# IndyShield.net
KiCad netlist of a schematic drawn in EAGLE
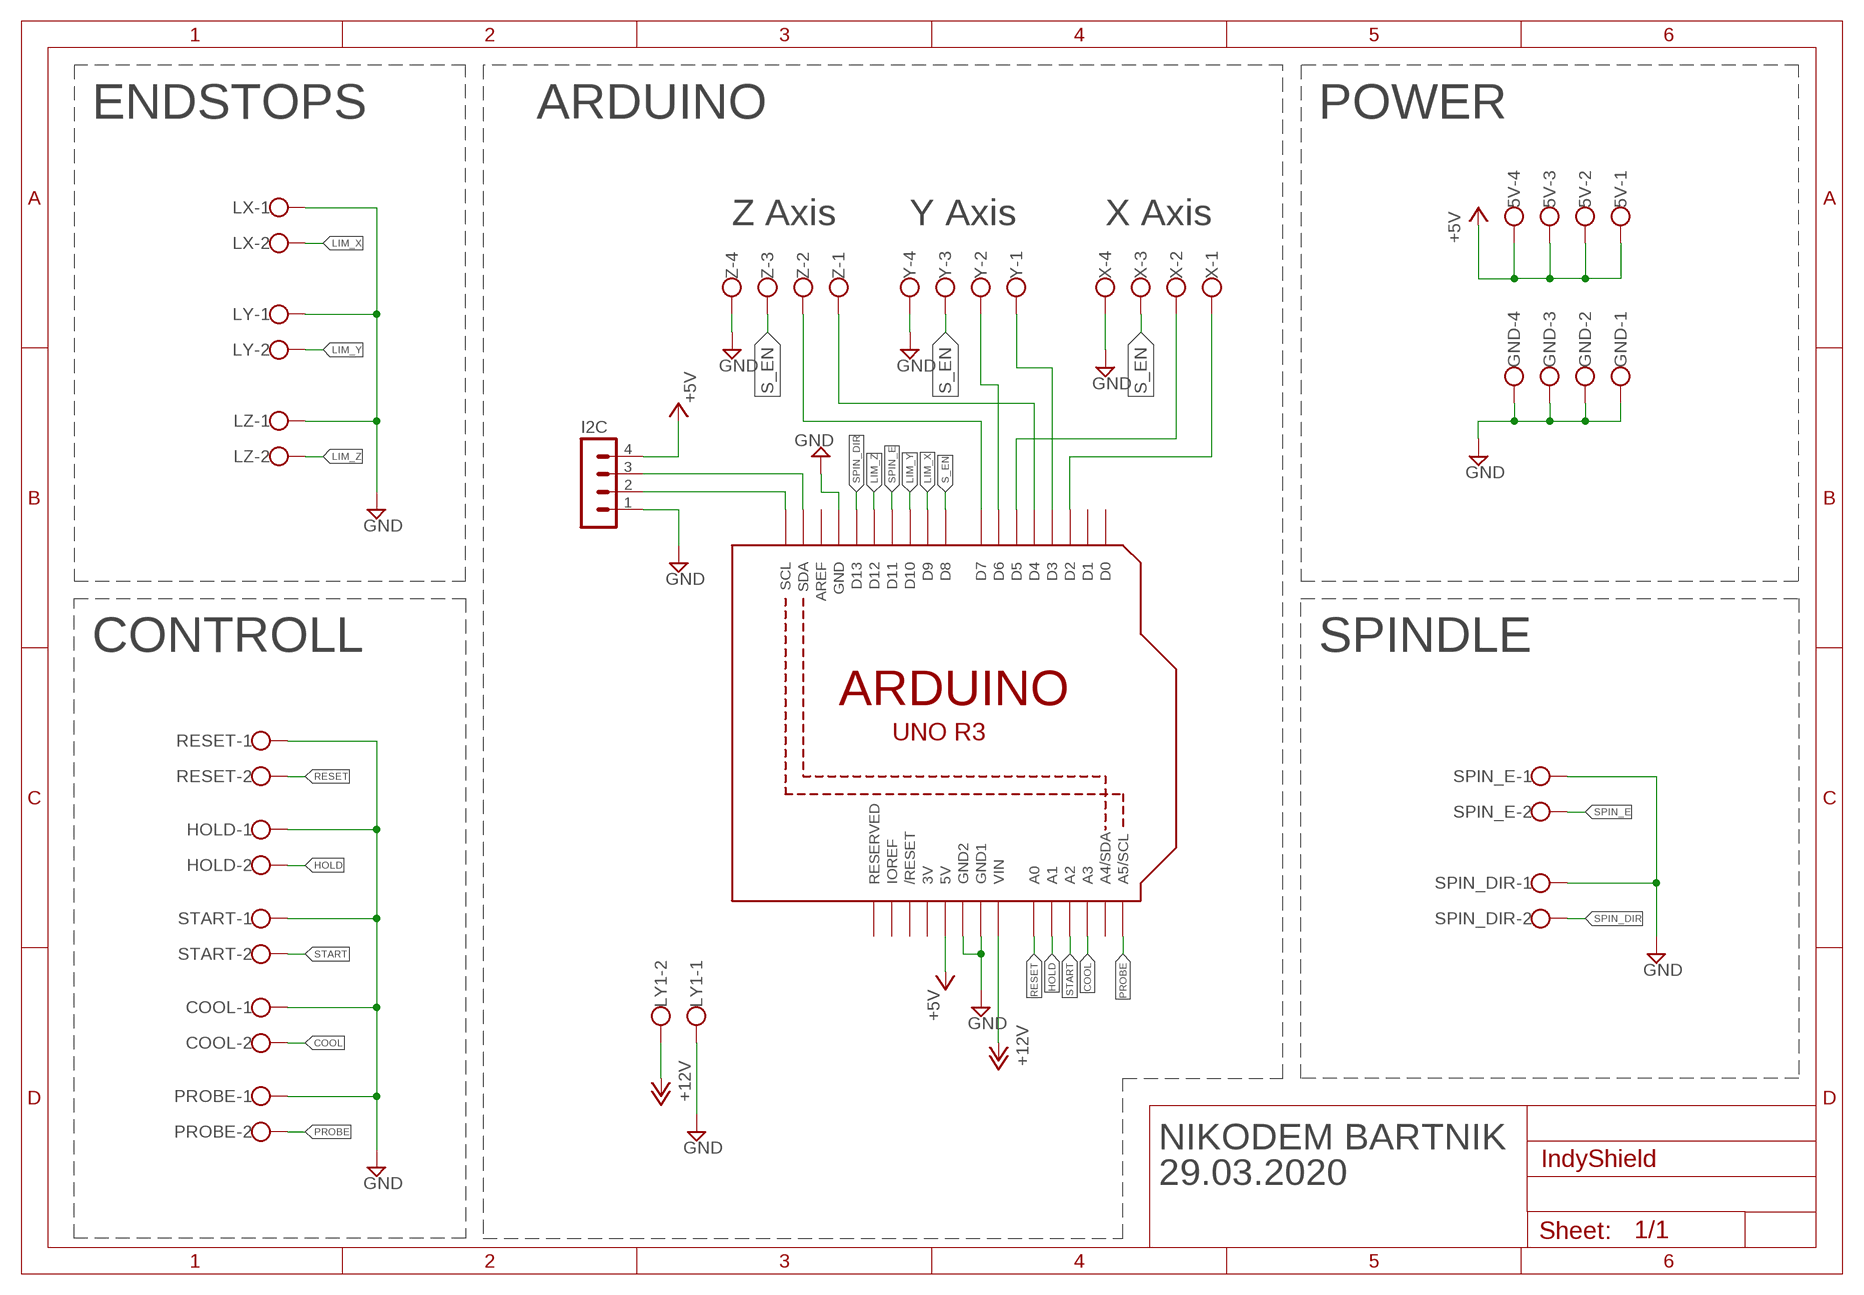
[diagram p0: schematic, sheet 1]

(export (version "E")
  (design (tool "Eeschema 10.0.6"))
  (components
    (comp (ref "5V")
      (value "W237-4")
      (footprint "eagle-import:W237-4")
      (libsource (lib "eagle-import") (part "W237-4"))
    )
    (comp (ref "COOL")
      (value "W237-102")
      (footprint "eagle-import:W237-102")
      (fields (field (name "MPN") "237-102"))
      (libsource (lib "eagle-import") (part "W237-102"))
    )
    (comp (ref "GND")
      (value "W237-4")
      (footprint "eagle-import:W237-4")
      (libsource (lib "eagle-import") (part "W237-4"))
    )
    (comp (ref "HOLD")
      (value "W237-102")
      (footprint "eagle-import:W237-102")
      (fields (field (name "MPN") "237-102"))
      (libsource (lib "eagle-import") (part "W237-102"))
    )
    (comp (ref "I2C")
      (value "MA04-1")
      (footprint "eagle-import:MA04-1")
      (libsource (lib "eagle-import") (part "MA04-1"))
    )
    (comp (ref "LX")
      (value "W237-102")
      (footprint "eagle-import:W237-102")
      (fields (field (name "MPN") "237-102"))
      (libsource (lib "eagle-import") (part "W237-102"))
    )
    (comp (ref "LY")
      (value "W237-102")
      (footprint "eagle-import:W237-102")
      (fields (field (name "MPN") "237-102"))
      (libsource (lib "eagle-import") (part "W237-102"))
    )
    (comp (ref "LY1")
      (value "W237-102")
      (footprint "eagle-import:W237-102")
      (fields (field (name "MPN") "237-102"))
      (libsource (lib "eagle-import") (part "W237-102"))
    )
    (comp (ref "LZ")
      (value "W237-102")
      (footprint "eagle-import:W237-102")
      (fields (field (name "MPN") "237-102"))
      (libsource (lib "eagle-import") (part "W237-102"))
    )
    (comp (ref "PROBE")
      (value "W237-102")
      (footprint "eagle-import:W237-102")
      (fields (field (name "MPN") "237-102"))
      (libsource (lib "eagle-import") (part "W237-102"))
    )
    (comp (ref "RESET")
      (value "W237-102")
      (footprint "eagle-import:W237-102")
      (fields (field (name "MPN") "237-102"))
      (libsource (lib "eagle-import") (part "W237-102"))
    )
    (comp (ref "SPIN_DIR")
      (value "W237-102")
      (footprint "eagle-import:W237-102")
      (fields (field (name "MPN") "237-102"))
      (libsource (lib "eagle-import") (part "W237-102"))
    )
    (comp (ref "SPIN_E")
      (value "W237-102")
      (footprint "eagle-import:W237-102")
      (fields (field (name "MPN") "237-102"))
      (libsource (lib "eagle-import") (part "W237-102"))
    )
    (comp (ref "START")
      (value "W237-102")
      (footprint "eagle-import:W237-102")
      (fields (field (name "MPN") "237-102"))
      (libsource (lib "eagle-import") (part "W237-102"))
    )
    (comp (ref "U1")
      (value "ARDUINOR3-BPLACE")
      (footprint "eagle-import:ARDUINOR3-BPLACE")
      (libsource (lib "eagle-import") (part "ARDUINOR3-BPLACE"))
    )
    (comp (ref "X")
      (value "W237-4")
      (footprint "eagle-import:W237-4")
      (libsource (lib "eagle-import") (part "W237-4"))
    )
    (comp (ref "Y")
      (value "W237-4")
      (footprint "eagle-import:W237-4")
      (libsource (lib "eagle-import") (part "W237-4"))
    )
    (comp (ref "Z")
      (value "W237-4")
      (footprint "eagle-import:W237-4")
      (libsource (lib "eagle-import") (part "W237-4"))
    )
  )
  (nets
    (net (code "1") (name "+5V") (class "Default")
      (node (ref "5V") (pin "1") (pinfunction "KL_1") (pintype "passive"))
      (node (ref "5V") (pin "2") (pinfunction "KL_2") (pintype "passive"))
      (node (ref "5V") (pin "3") (pinfunction "KL_3") (pintype "passive"))
      (node (ref "5V") (pin "4") (pinfunction "KL_4") (pintype "passive"))
      (node (ref "I2C") (pin "4") (pinfunction "4_4") (pintype "passive"))
      (node (ref "U1") (pin "5V") (pinfunction "5V_5V") (pintype "power_in"))
    )
    (net (code "2") (name "+12V") (class "Default")
      (node (ref "LY1") (pin "2") (pinfunction "KL_2") (pintype "passive"))
      (node (ref "U1") (pin "VIN") (pinfunction "VIN_VIN") (pintype "power_in"))
    )
    (net (code "3") (name "/3V") (class "Default")
      (node (ref "U1") (pin "3V") (pinfunction "3V_3V") (pintype "power_in"))
    )
    (net (code "4") (name "COOL") (class "Default")
      (node (ref "COOL") (pin "2") (pinfunction "KL_2") (pintype "passive"))
      (node (ref "U1") (pin "A3") (pinfunction "A3_A3") (pintype "bidirectional"))
    )
    (net (code "5") (name "GND") (class "Default")
      (node (ref "COOL") (pin "1") (pinfunction "KL_1") (pintype "passive"))
      (node (ref "GND") (pin "1") (pinfunction "KL_1") (pintype "passive"))
      (node (ref "GND") (pin "2") (pinfunction "KL_2") (pintype "passive"))
      (node (ref "GND") (pin "3") (pinfunction "KL_3") (pintype "passive"))
      (node (ref "GND") (pin "4") (pinfunction "KL_4") (pintype "passive"))
      (node (ref "HOLD") (pin "1") (pinfunction "KL_1") (pintype "passive"))
      (node (ref "I2C") (pin "1") (pinfunction "1_1") (pintype "passive"))
      (node (ref "LX") (pin "1") (pinfunction "KL_1") (pintype "passive"))
      (node (ref "LY") (pin "1") (pinfunction "KL_1") (pintype "passive"))
      (node (ref "LY1") (pin "1") (pinfunction "KL_1") (pintype "passive"))
      (node (ref "LZ") (pin "1") (pinfunction "KL_1") (pintype "passive"))
      (node (ref "PROBE") (pin "1") (pinfunction "KL_1") (pintype "passive"))
      (node (ref "RESET") (pin "1") (pinfunction "KL_1") (pintype "passive"))
      (node (ref "SPIN_DIR") (pin "1") (pinfunction "KL_1") (pintype "passive"))
      (node (ref "SPIN_E") (pin "1") (pinfunction "KL_1") (pintype "passive"))
      (node (ref "START") (pin "1") (pinfunction "KL_1") (pintype "passive"))
      (node (ref "U1") (pin "GND") (pinfunction "GND_GND") (pintype "power_in"))
      (node (ref "U1") (pin "GND1") (pinfunction "GND1_GND1") (pintype "power_in"))
      (node (ref "U1") (pin "GND2") (pinfunction "GND2_GND2") (pintype "power_in"))
      (node (ref "X") (pin "4") (pinfunction "KL_4") (pintype "passive"))
      (node (ref "Y") (pin "4") (pinfunction "KL_4") (pintype "passive"))
      (node (ref "Z") (pin "4") (pinfunction "KL_4") (pintype "passive"))
    )
    (net (code "6") (name "HOLD") (class "Default")
      (node (ref "HOLD") (pin "2") (pinfunction "KL_2") (pintype "passive"))
      (node (ref "U1") (pin "A1") (pinfunction "A1_A1") (pintype "bidirectional"))
    )
    (net (code "7") (name "LIM_X") (class "Default")
      (node (ref "LX") (pin "2") (pinfunction "KL_2") (pintype "passive"))
      (node (ref "U1") (pin "D9") (pinfunction "D9_D9") (pintype "bidirectional"))
    )
    (net (code "8") (name "LIM_Y") (class "Default")
      (node (ref "LY") (pin "2") (pinfunction "KL_2") (pintype "passive"))
      (node (ref "U1") (pin "D10") (pinfunction "D10_D10") (pintype "bidirectional"))
    )
    (net (code "9") (name "LIM_Z") (class "Default")
      (node (ref "LZ") (pin "2") (pinfunction "KL_2") (pintype "passive"))
      (node (ref "U1") (pin "D12") (pinfunction "D12_D12") (pintype "bidirectional"))
    )
    (net (code "10") (name "Net-(I2C-Pad2)") (class "Default")
      (node (ref "I2C") (pin "2") (pinfunction "2_2") (pintype "passive"))
      (node (ref "U1") (pin "SCL") (pinfunction "SCL_SCL") (pintype "bidirectional"))
    )
    (net (code "11") (name "Net-(I2C-Pad3)") (class "Default")
      (node (ref "I2C") (pin "3") (pinfunction "3_3") (pintype "passive"))
      (node (ref "U1") (pin "SDA") (pinfunction "SDA_SDA") (pintype "bidirectional"))
    )
    (net (code "12") (name "Net-(XA-KL)") (class "Default")
      (node (ref "U1") (pin "D2") (pinfunction "D2_D2") (pintype "bidirectional"))
      (node (ref "X") (pin "1") (pinfunction "KL_1") (pintype "passive"))
    )
    (net (code "13") (name "Net-(XB-KL)") (class "Default")
      (node (ref "U1") (pin "D5") (pinfunction "D5_D5") (pintype "bidirectional"))
      (node (ref "X") (pin "2") (pinfunction "KL_2") (pintype "passive"))
    )
    (net (code "14") (name "Net-(YA-KL)") (class "Default")
      (node (ref "U1") (pin "D3") (pinfunction "D3_D3") (pintype "bidirectional"))
      (node (ref "Y") (pin "1") (pinfunction "KL_1") (pintype "passive"))
    )
    (net (code "15") (name "Net-(YB-KL)") (class "Default")
      (node (ref "U1") (pin "D6") (pinfunction "D6_D6") (pintype "bidirectional"))
      (node (ref "Y") (pin "2") (pinfunction "KL_2") (pintype "passive"))
    )
    (net (code "16") (name "Net-(ZA-KL)") (class "Default")
      (node (ref "U1") (pin "D4") (pinfunction "D4_D4") (pintype "bidirectional"))
      (node (ref "Z") (pin "1") (pinfunction "KL_1") (pintype "passive"))
    )
    (net (code "17") (name "Net-(ZB-KL)") (class "Default")
      (node (ref "U1") (pin "D7") (pinfunction "D7_D7") (pintype "bidirectional"))
      (node (ref "Z") (pin "2") (pinfunction "KL_2") (pintype "passive"))
    )
    (net (code "18") (name "PROBE") (class "Default")
      (node (ref "PROBE") (pin "2") (pinfunction "KL_2") (pintype "passive"))
      (node (ref "U1") (pin "A5") (pinfunction "A5/SCL_A5") (pintype "bidirectional"))
    )
    (net (code "19") (name "RESET") (class "Default")
      (node (ref "RESET") (pin "2") (pinfunction "KL_2") (pintype "passive"))
      (node (ref "U1") (pin "A0") (pinfunction "A0_A0") (pintype "bidirectional"))
    )
    (net (code "20") (name "SPIN_DIR") (class "Default")
      (node (ref "SPIN_DIR") (pin "2") (pinfunction "KL_2") (pintype "passive"))
      (node (ref "U1") (pin "D13") (pinfunction "D13_D13") (pintype "bidirectional"))
    )
    (net (code "21") (name "SPIN_E") (class "Default")
      (node (ref "SPIN_E") (pin "2") (pinfunction "KL_2") (pintype "passive"))
      (node (ref "U1") (pin "D11") (pinfunction "D11_D11") (pintype "bidirectional"))
    )
    (net (code "22") (name "START") (class "Default")
      (node (ref "START") (pin "2") (pinfunction "KL_2") (pintype "passive"))
      (node (ref "U1") (pin "A2") (pinfunction "A2_A2") (pintype "bidirectional"))
    )
    (net (code "23") (name "S_EN") (class "Default")
      (node (ref "U1") (pin "D8") (pinfunction "D8_D8") (pintype "bidirectional"))
      (node (ref "X") (pin "3") (pinfunction "KL_3") (pintype "passive"))
      (node (ref "Y") (pin "3") (pinfunction "KL_3") (pintype "passive"))
      (node (ref "Z") (pin "3") (pinfunction "KL_3") (pintype "passive"))
    )
    (net (code "24") (name "unconnected-(U1-A4{slash}SDA-PadA4)") (class "Default")
      (node (ref "U1") (pin "A4") (pinfunction "A4/SDA_A4") (pintype "bidirectional"))
    )
    (net (code "25") (name "unconnected-(U1-PadAREF)") (class "Default")
      (node (ref "U1") (pin "AREF") (pinfunction "AREF_AREF") (pintype "bidirectional"))
    )
    (net (code "26") (name "unconnected-(U1-PadD0)") (class "Default")
      (node (ref "U1") (pin "D0") (pinfunction "D0_D0") (pintype "bidirectional"))
    )
    (net (code "27") (name "unconnected-(U1-PadD1)") (class "Default")
      (node (ref "U1") (pin "D1") (pinfunction "D1_D1") (pintype "bidirectional"))
    )
    (net (code "28") (name "unconnected-(U1-PadIOREF)") (class "Default")
      (node (ref "U1") (pin "IOREF") (pinfunction "IOREF_IOREF") (pintype "output"))
    )
    (net (code "29") (name "unconnected-(U1-PadRESERVED)") (class "Default")
      (node (ref "U1") (pin "RESERVED") (pinfunction "RESERVED_RESERVED") (pintype "no_connect"))
    )
    (net (code "30") (name "unconnected-(U1-{slash}RESET-PadRESET)") (class "Default")
      (node (ref "U1") (pin "RESET") (pinfunction "/RESET_RESET") (pintype "bidirectional"))
    )
  )
)
